# PICv2.net
KiCad netlist of a schematic drawn in EAGLE
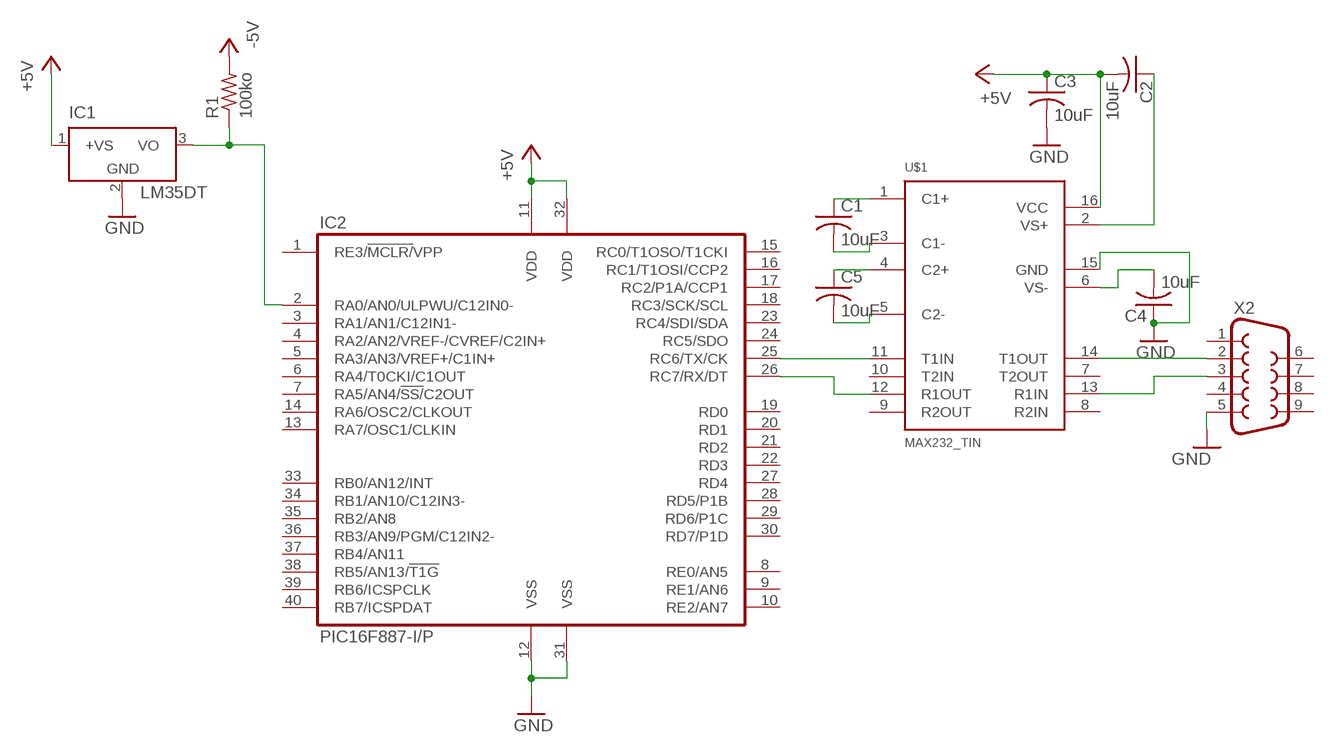
[diagram p0: schematic, sheet 1]

(export (version "E")
  (design (tool "Eeschema 10.0.6"))
  (components
    (comp (ref "C1")
      (value "10uF")
      (footprint "eagle-import:C0805")
      (fields (field (name "MPN") "CGA2B1X7R1C104K050BC"))
      (libsource (lib "eagle-import") (part "C-USC0805"))
    )
    (comp (ref "C2")
      (value "10uF")
      (footprint "eagle-import:C0805")
      (fields (field (name "MPN") "CGA2B1X7R1C104K050BC"))
      (libsource (lib "eagle-import") (part "C-USC0805"))
    )
    (comp (ref "C3")
      (value "10uF")
      (footprint "eagle-import:C0805")
      (fields (field (name "MPN") "CGA2B1X7R1C104K050BC"))
      (libsource (lib "eagle-import") (part "C-USC0805"))
    )
    (comp (ref "C4")
      (value "10uF")
      (footprint "eagle-import:C0805")
      (fields (field (name "MPN") "CGA2B1X7R1C104K050BC"))
      (libsource (lib "eagle-import") (part "C-USC0805"))
    )
    (comp (ref "C5")
      (value "10uF")
      (footprint "eagle-import:C0805")
      (fields (field (name "MPN") "CGA2B1X7R1C104K050BC"))
      (libsource (lib "eagle-import") (part "C-USC0805"))
    )
    (comp (ref "IC1")
      (value "LM35DT")
      (footprint "eagle-import:TO220V")
      (fields (field (name "MF") "NATIONAL SEMICONDUCTOR") (field (name "MPN") "LM35AH"))
      (libsource (lib "eagle-import") (part "LM35DT"))
    )
    (comp (ref "IC2")
      (value "PIC16F887-I/P")
      (footprint "eagle-import:DIL40")
      (libsource (lib "eagle-import") (part "PIC16F887-I/P"))
    )
    (comp (ref "R1")
      (value "100ko")
      (footprint "eagle-import:M0805")
      (fields (field (name "MPN") "ERJ-1GNF1003C"))
      (libsource (lib "eagle-import") (part "R-US_M0805"))
    )
    (comp (ref "U$1")
      (value "MAX232_TIN")
      (footprint "eagle-import:DIL16")
      (fields (field (name "MPN") "MAX232EIDR"))
      (libsource (lib "eagle-import") (part "MAX232_TIN"))
    )
    (comp (ref "X2")
      (value "F09D")
      (footprint "eagle-import:F09D")
      (libsource (lib "eagle-import") (part "F09D"))
    )
  )
  (nets
    (net (code "1") (name "+5V") (class "Default")
      (node (ref "C2") (pin "2") (pinfunction "2_2") (pintype "passive"))
      (node (ref "C3") (pin "1") (pinfunction "1_1") (pintype "passive"))
      (node (ref "IC1") (pin "1") (pinfunction "+VS_1") (pintype "input"))
      (node (ref "IC2") (pin "11") (pinfunction "VDD_11") (pintype "power_in"))
      (node (ref "IC2") (pin "32") (pinfunction "VDD_32") (pintype "power_in"))
      (node (ref "U$1") (pin "16") (pinfunction "VCC_16") (pintype "bidirectional"))
    )
    (net (code "2") (name "-5V") (class "Default")
      (node (ref "R1") (pin "2") (pinfunction "2_2") (pintype "passive"))
    )
    (net (code "3") (name "GND") (class "Default")
      (node (ref "C3") (pin "2") (pinfunction "2_2") (pintype "passive"))
      (node (ref "C4") (pin "1") (pinfunction "1_1") (pintype "passive"))
      (node (ref "IC1") (pin "2") (pinfunction "GND_2") (pintype "power_in"))
      (node (ref "IC2") (pin "12") (pinfunction "VSS_12") (pintype "power_in"))
      (node (ref "IC2") (pin "31") (pinfunction "VSS_31") (pintype "power_in"))
      (node (ref "U$1") (pin "15") (pinfunction "GND_15") (pintype "bidirectional"))
      (node (ref "X2") (pin "5") (pinfunction "5_5") (pintype "passive"))
    )
    (net (code "4") (name "Net-(IC1-VO)") (class "Default")
      (node (ref "IC1") (pin "3") (pinfunction "VO_3") (pintype "input"))
      (node (ref "IC2") (pin "2") (pinfunction "RA0/AN0/ULPWU/C12IN0-_2") (pintype "bidirectional"))
      (node (ref "R1") (pin "1") (pinfunction "1_1") (pintype "passive"))
    )
    (net (code "5") (name "Net-(IC2-RC6{slash}TX{slash}CK)") (class "Default")
      (node (ref "IC2") (pin "25") (pinfunction "RC6/TX/CK_25") (pintype "bidirectional"))
      (node (ref "U$1") (pin "11") (pinfunction "T1IN_11") (pintype "bidirectional"))
    )
    (net (code "6") (name "Net-(IC2-RC7{slash}RX{slash}DT)") (class "Default")
      (node (ref "IC2") (pin "26") (pinfunction "RC7/RX/DT_26") (pintype "bidirectional"))
      (node (ref "U$1") (pin "12") (pinfunction "R1OUT_12") (pintype "bidirectional"))
    )
    (net (code "7") (name "Net-(U$1-C1+)") (class "Default")
      (node (ref "C1") (pin "1") (pinfunction "1_1") (pintype "passive"))
      (node (ref "U$1") (pin "1") (pinfunction "C1+_1") (pintype "bidirectional"))
    )
    (net (code "8") (name "Net-(U$1-C1-)") (class "Default")
      (node (ref "C1") (pin "2") (pinfunction "2_2") (pintype "passive"))
      (node (ref "U$1") (pin "3") (pinfunction "C1-_3") (pintype "bidirectional"))
    )
    (net (code "9") (name "Net-(U$1-C2+)") (class "Default")
      (node (ref "C5") (pin "1") (pinfunction "1_1") (pintype "passive"))
      (node (ref "U$1") (pin "4") (pinfunction "C2+_4") (pintype "bidirectional"))
    )
    (net (code "10") (name "Net-(U$1-C2-)") (class "Default")
      (node (ref "C5") (pin "2") (pinfunction "2_2") (pintype "passive"))
      (node (ref "U$1") (pin "5") (pinfunction "C2-_5") (pintype "bidirectional"))
    )
    (net (code "11") (name "Net-(U$1-R1IN)") (class "Default")
      (node (ref "U$1") (pin "13") (pinfunction "R1IN_13") (pintype "bidirectional"))
      (node (ref "X2") (pin "3") (pinfunction "3_3") (pintype "passive"))
    )
    (net (code "12") (name "Net-(U$1-T1OUT)") (class "Default")
      (node (ref "U$1") (pin "14") (pinfunction "T1OUT_14") (pintype "bidirectional"))
      (node (ref "X2") (pin "2") (pinfunction "2_2") (pintype "passive"))
    )
    (net (code "13") (name "Net-(U$1-VS+)") (class "Default")
      (node (ref "C2") (pin "1") (pinfunction "1_1") (pintype "passive"))
      (node (ref "U$1") (pin "2") (pinfunction "VS+_2") (pintype "bidirectional"))
    )
    (net (code "14") (name "Net-(U$1-VS-)") (class "Default")
      (node (ref "C4") (pin "2") (pinfunction "2_2") (pintype "passive"))
      (node (ref "U$1") (pin "6") (pinfunction "VS-_6") (pintype "bidirectional"))
    )
    (net (code "15") (name "unconnected-(IC2-RA1{slash}AN1{slash}C12IN1--Pad3)") (class "Default")
      (node (ref "IC2") (pin "3") (pinfunction "RA1/AN1/C12IN1-_3") (pintype "bidirectional"))
    )
    (net (code "16") (name "unconnected-(IC2-RA2{slash}AN2{slash}VREF-{slash}CVREF{slash}C2IN+-Pad4)") (class "Default")
      (node (ref "IC2") (pin "4") (pinfunction "RA2/AN2/VREF-/CVREF/C2IN+_4") (pintype "bidirectional"))
    )
    (net (code "17") (name "unconnected-(IC2-RA3{slash}AN3{slash}VREF+{slash}C1IN+-Pad5)") (class "Default")
      (node (ref "IC2") (pin "5") (pinfunction "RA3/AN3/VREF+/C1IN+_5") (pintype "bidirectional"))
    )
    (net (code "18") (name "unconnected-(IC2-RA4{slash}T0CKI{slash}C1OUT-Pad6)") (class "Default")
      (node (ref "IC2") (pin "6") (pinfunction "RA4/T0CKI/C1OUT_6") (pintype "bidirectional"))
    )
    (net (code "19") (name "unconnected-(IC2-RA5{slash}AN4{slash}~{SS{slash}}C2OUT-Pad7)") (class "Default")
      (node (ref "IC2") (pin "7") (pinfunction "RA5/AN4/~{SS/}C2OUT_7") (pintype "bidirectional"))
    )
    (net (code "20") (name "unconnected-(IC2-RA6{slash}OSC2{slash}CLKOUT-Pad14)") (class "Default")
      (node (ref "IC2") (pin "14") (pinfunction "RA6/OSC2/CLKOUT_14") (pintype "bidirectional"))
    )
    (net (code "21") (name "unconnected-(IC2-RA7{slash}OSC1{slash}CLKIN-Pad13)") (class "Default")
      (node (ref "IC2") (pin "13") (pinfunction "RA7/OSC1/CLKIN_13") (pintype "bidirectional"))
    )
    (net (code "22") (name "unconnected-(IC2-RB0{slash}AN12{slash}INT-Pad33)") (class "Default")
      (node (ref "IC2") (pin "33") (pinfunction "RB0/AN12/INT_33") (pintype "bidirectional"))
    )
    (net (code "23") (name "unconnected-(IC2-RB1{slash}AN10{slash}C12IN3--Pad34)") (class "Default")
      (node (ref "IC2") (pin "34") (pinfunction "RB1/AN10/C12IN3-_34") (pintype "bidirectional"))
    )
    (net (code "24") (name "unconnected-(IC2-RB2{slash}AN8-Pad35)") (class "Default")
      (node (ref "IC2") (pin "35") (pinfunction "RB2/AN8_35") (pintype "bidirectional"))
    )
    (net (code "25") (name "unconnected-(IC2-RB3{slash}AN9{slash}PGM{slash}C12IN2--Pad36)") (class "Default")
      (node (ref "IC2") (pin "36") (pinfunction "RB3/AN9/PGM/C12IN2-_36") (pintype "bidirectional"))
    )
    (net (code "26") (name "unconnected-(IC2-RB4{slash}AN11-Pad37)") (class "Default")
      (node (ref "IC2") (pin "37") (pinfunction "RB4/AN11_37") (pintype "bidirectional"))
    )
    (net (code "27") (name "unconnected-(IC2-RB5{slash}AN13{slash}~{T1G}-Pad38)") (class "Default")
      (node (ref "IC2") (pin "38") (pinfunction "RB5/AN13/~{T1G}_38") (pintype "bidirectional"))
    )
    (net (code "28") (name "unconnected-(IC2-RB6{slash}ICSPCLK-Pad39)") (class "Default")
      (node (ref "IC2") (pin "39") (pinfunction "RB6/ICSPCLK_39") (pintype "bidirectional"))
    )
    (net (code "29") (name "unconnected-(IC2-RB7{slash}ICSPDAT-Pad40)") (class "Default")
      (node (ref "IC2") (pin "40") (pinfunction "RB7/ICSPDAT_40") (pintype "bidirectional"))
    )
    (net (code "30") (name "unconnected-(IC2-RC0{slash}T1OSO{slash}T1CKI-Pad15)") (class "Default")
      (node (ref "IC2") (pin "15") (pinfunction "RC0/T1OSO/T1CKI_15") (pintype "bidirectional"))
    )
    (net (code "31") (name "unconnected-(IC2-RC1{slash}T1OSI{slash}CCP2-Pad16)") (class "Default")
      (node (ref "IC2") (pin "16") (pinfunction "RC1/T1OSI/CCP2_16") (pintype "bidirectional"))
    )
    (net (code "32") (name "unconnected-(IC2-RC2{slash}P1A{slash}CCP1-Pad17)") (class "Default")
      (node (ref "IC2") (pin "17") (pinfunction "RC2/P1A/CCP1_17") (pintype "bidirectional"))
    )
    (net (code "33") (name "unconnected-(IC2-RC3{slash}SCK{slash}SCL-Pad18)") (class "Default")
      (node (ref "IC2") (pin "18") (pinfunction "RC3/SCK/SCL_18") (pintype "bidirectional"))
    )
    (net (code "34") (name "unconnected-(IC2-RC4{slash}SDI{slash}SDA-Pad23)") (class "Default")
      (node (ref "IC2") (pin "23") (pinfunction "RC4/SDI/SDA_23") (pintype "bidirectional"))
    )
    (net (code "35") (name "unconnected-(IC2-RC5{slash}SDO-Pad24)") (class "Default")
      (node (ref "IC2") (pin "24") (pinfunction "RC5/SDO_24") (pintype "bidirectional"))
    )
    (net (code "36") (name "unconnected-(IC2-RD0-Pad19)") (class "Default")
      (node (ref "IC2") (pin "19") (pinfunction "RD0_19") (pintype "bidirectional"))
    )
    (net (code "37") (name "unconnected-(IC2-RD1-Pad20)") (class "Default")
      (node (ref "IC2") (pin "20") (pinfunction "RD1_20") (pintype "bidirectional"))
    )
    (net (code "38") (name "unconnected-(IC2-RD2-Pad21)") (class "Default")
      (node (ref "IC2") (pin "21") (pinfunction "RD2_21") (pintype "bidirectional"))
    )
    (net (code "39") (name "unconnected-(IC2-RD3-Pad22)") (class "Default")
      (node (ref "IC2") (pin "22") (pinfunction "RD3_22") (pintype "bidirectional"))
    )
    (net (code "40") (name "unconnected-(IC2-RD4-Pad27)") (class "Default")
      (node (ref "IC2") (pin "27") (pinfunction "RD4_27") (pintype "bidirectional"))
    )
    (net (code "41") (name "unconnected-(IC2-RD5{slash}P1B-Pad28)") (class "Default")
      (node (ref "IC2") (pin "28") (pinfunction "RD5/P1B_28") (pintype "bidirectional"))
    )
    (net (code "42") (name "unconnected-(IC2-RD6{slash}P1C-Pad29)") (class "Default")
      (node (ref "IC2") (pin "29") (pinfunction "RD6/P1C_29") (pintype "bidirectional"))
    )
    (net (code "43") (name "unconnected-(IC2-RD7{slash}P1D-Pad30)") (class "Default")
      (node (ref "IC2") (pin "30") (pinfunction "RD7/P1D_30") (pintype "bidirectional"))
    )
    (net (code "44") (name "unconnected-(IC2-RE0{slash}AN5-Pad8)") (class "Default")
      (node (ref "IC2") (pin "8") (pinfunction "RE0/AN5_8") (pintype "bidirectional"))
    )
    (net (code "45") (name "unconnected-(IC2-RE1{slash}AN6-Pad9)") (class "Default")
      (node (ref "IC2") (pin "9") (pinfunction "RE1/AN6_9") (pintype "bidirectional"))
    )
    (net (code "46") (name "unconnected-(IC2-RE2{slash}AN7-Pad10)") (class "Default")
      (node (ref "IC2") (pin "10") (pinfunction "RE2/AN7_10") (pintype "bidirectional"))
    )
    (net (code "47") (name "unconnected-(IC2-RE3{slash}~{MCLR{slash}}VPP-Pad1)") (class "Default")
      (node (ref "IC2") (pin "1") (pinfunction "RE3/~{MCLR/}VPP_1") (pintype "input"))
    )
    (net (code "48") (name "unconnected-(U$1-R2IN-Pad8)") (class "Default")
      (node (ref "U$1") (pin "8") (pinfunction "R2IN_8") (pintype "bidirectional"))
    )
    (net (code "49") (name "unconnected-(U$1-R2OUT-Pad9)") (class "Default")
      (node (ref "U$1") (pin "9") (pinfunction "R2OUT_9") (pintype "bidirectional"))
    )
    (net (code "50") (name "unconnected-(U$1-T2IN-Pad10)") (class "Default")
      (node (ref "U$1") (pin "10") (pinfunction "T2IN_10") (pintype "bidirectional"))
    )
    (net (code "51") (name "unconnected-(U$1-T2OUT-Pad7)") (class "Default")
      (node (ref "U$1") (pin "7") (pinfunction "T2OUT_7") (pintype "bidirectional"))
    )
    (net (code "52") (name "unconnected-(X2-Pad1)") (class "Default")
      (node (ref "X2") (pin "1") (pinfunction "1_1") (pintype "passive"))
    )
    (net (code "53") (name "unconnected-(X2-Pad4)") (class "Default")
      (node (ref "X2") (pin "4") (pinfunction "4_4") (pintype "passive"))
    )
    (net (code "54") (name "unconnected-(X2-Pad6)") (class "Default")
      (node (ref "X2") (pin "6") (pinfunction "6_6") (pintype "passive"))
    )
    (net (code "55") (name "unconnected-(X2-Pad7)") (class "Default")
      (node (ref "X2") (pin "7") (pinfunction "7_7") (pintype "passive"))
    )
    (net (code "56") (name "unconnected-(X2-Pad8)") (class "Default")
      (node (ref "X2") (pin "8") (pinfunction "8_8") (pintype "passive"))
    )
    (net (code "57") (name "unconnected-(X2-Pad9)") (class "Default")
      (node (ref "X2") (pin "9") (pinfunction "9_9") (pintype "passive"))
    )
  )
)
